# GNSS.net
KiCad netlist of a schematic drawn in Altium Designer
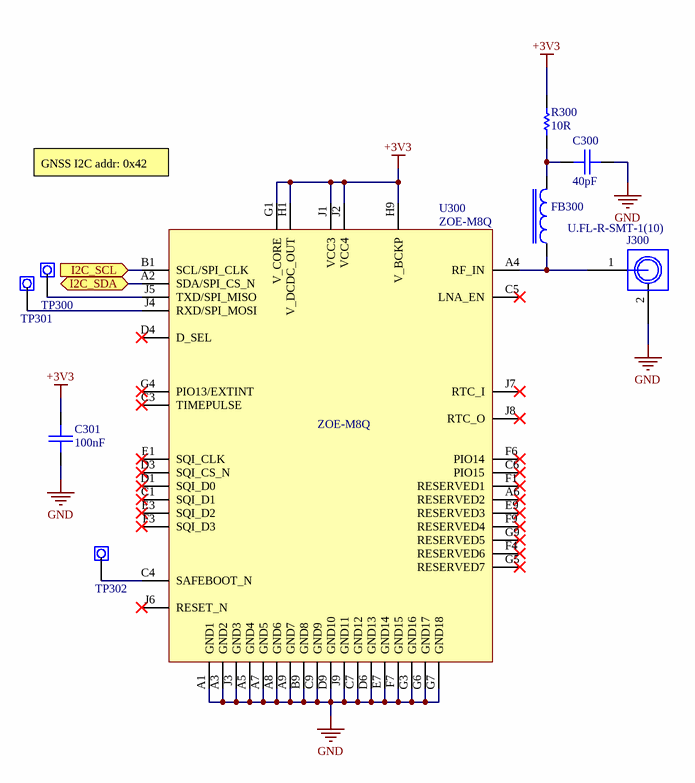
[diagram p0: GNSS.SchDoc]

(export (version "E")
  (design (tool "Eeschema 10.0.6"))
  (components
    (comp (ref "C300")
      (value "40pF")
      (footprint "0603_CAP")
      (libsource (lib "Moonlight_Components") (part "Capacitor"))
    )
    (comp (ref "C301")
      (value "100nF")
      (footprint "0603_CAP")
      (libsource (lib "Moonlight_Components") (part "Capacitor"))
    )
    (comp (ref "FB300")
      (value "FBTH1608HL221-T")
      (footprint "0603_FERRITE")
      (description "Digikey part no.\r\n587-FBTH1608HL221-TCT-ND")
      (libsource (lib "Moonlight_Components") (part "Ferrite Bead"))
    )
    (comp (ref "J300")
      (value "U.FL-R-SMT-1(10)")
      (footprint "U.FL-R-SMT-1(10)")
      (description "Digikey part no. H11891CT-ND")
      (libsource (lib "Moonlight_Components") (part "U.FL SMD"))
    )
    (comp (ref "R300")
      (value "10R")
      (footprint "0603_RES")
      (libsource (lib "Moonlight_Components") (part "Resistor"))
    )
    (comp (ref "TP300")
      (value "GPS_TX")
      (footprint "Testpoint")
      (libsource (lib "Moonlight_Components") (part "Testpoint"))
    )
    (comp (ref "TP301")
      (value "GPS_RX")
      (footprint "Testpoint")
      (libsource (lib "Moonlight_Components") (part "Testpoint"))
    )
    (comp (ref "TP302")
      (value "GPS_SAFEBOOT")
      (footprint "Testpoint2")
      (libsource (lib "Moonlight_Components") (part "Testpoint"))
    )
    (comp (ref "U300")
      (value "ZOE-M8Q")
      (footprint "ZOE-M8Q")
      (description "u-blox ZOE GNSS module")
      (fields (field (name "MANUFACTURER") "u-blox"))
      (libsource (lib "Moonlight_Components") (part "ZOE-M8Q"))
    )
  )
  (nets
    (net (code "1") (name "+3V3") (class "Default")
      (node (ref "C301") (pin "1") (pinfunction "1_1") (pintype "passive"))
      (node (ref "R300") (pin "1") (pinfunction "1_1") (pintype "passive"))
      (node (ref "U300") (pin "G1") (pinfunction "V_CORE_G1") (pintype "passive"))
      (node (ref "U300") (pin "H1") (pinfunction "V_DCDC_OUT_H1") (pintype "passive"))
      (node (ref "U300") (pin "H9") (pinfunction "V_BCKP_H9") (pintype "passive"))
      (node (ref "U300") (pin "J1") (pinfunction "VCC3_J1") (pintype "passive"))
      (node (ref "U300") (pin "J2") (pinfunction "VCC4_J2") (pintype "passive"))
    )
    (net (code "2") (name "/I2C_SCL") (class "Default")
      (node (ref "U300") (pin "B1") (pinfunction "SCL/SPI_CLK_B1") (pintype "passive"))
    )
    (net (code "3") (name "/I2C_SDA") (class "Default")
      (node (ref "U300") (pin "A2") (pinfunction "SDA/SPI_CS_N_A2") (pintype "passive"))
    )
    (net (code "4") (name "GND") (class "Default")
      (node (ref "C300") (pin "2") (pinfunction "2_2") (pintype "passive"))
      (node (ref "C301") (pin "2") (pinfunction "2_2") (pintype "passive"))
      (node (ref "J300") (pin "2") (pinfunction "GND_2") (pintype "passive"))
      (node (ref "U300") (pin "A1") (pinfunction "GND1_A1") (pintype "passive"))
      (node (ref "U300") (pin "A3") (pinfunction "GND2_A3") (pintype "passive"))
      (node (ref "U300") (pin "A5") (pinfunction "GND4_A5") (pintype "passive"))
      (node (ref "U300") (pin "A7") (pinfunction "GND5_A7") (pintype "passive"))
      (node (ref "U300") (pin "A8") (pinfunction "GND6_A8") (pintype "passive"))
      (node (ref "U300") (pin "A9") (pinfunction "GND7_A9") (pintype "passive"))
      (node (ref "U300") (pin "B9") (pinfunction "GND8_B9") (pintype "passive"))
      (node (ref "U300") (pin "C7") (pinfunction "GND12_C7") (pintype "passive"))
      (node (ref "U300") (pin "C9") (pinfunction "GND9_C9") (pintype "passive"))
      (node (ref "U300") (pin "D6") (pinfunction "GND13_D6") (pintype "passive"))
      (node (ref "U300") (pin "D9") (pinfunction "GND10_D9") (pintype "passive"))
      (node (ref "U300") (pin "E7") (pinfunction "GND14_E7") (pintype "passive"))
      (node (ref "U300") (pin "F7") (pinfunction "GND15_F7") (pintype "passive"))
      (node (ref "U300") (pin "G3") (pinfunction "GND16_G3") (pintype "passive"))
      (node (ref "U300") (pin "G6") (pinfunction "GND17_G6") (pintype "passive"))
      (node (ref "U300") (pin "G7") (pinfunction "GND18_G7") (pintype "passive"))
      (node (ref "U300") (pin "J3") (pinfunction "GND3_J3") (pintype "passive"))
      (node (ref "U300") (pin "J9") (pinfunction "GND11_J9") (pintype "passive"))
    )
    (net (code "5") (name "Net-(C300-Pad1)") (class "Default")
      (node (ref "C300") (pin "1") (pinfunction "1_1") (pintype "passive"))
      (node (ref "FB300") (pin "2") (pinfunction "2_2") (pintype "passive"))
      (node (ref "R300") (pin "2") (pinfunction "2_2") (pintype "passive"))
    )
    (net (code "6") (name "Net-(J300-SIG)") (class "Default")
      (node (ref "FB300") (pin "1") (pinfunction "1_1") (pintype "passive"))
      (node (ref "J300") (pin "1") (pinfunction "SIG_1") (pintype "passive"))
      (node (ref "U300") (pin "A4") (pinfunction "RF_IN_A4") (pintype "passive"))
    )
    (net (code "7") (name "Net-(U300-RXD{slash}SPI_MOSI)") (class "Default")
      (node (ref "TP301") (pin "1") (pinfunction "1_1") (pintype "passive"))
      (node (ref "U300") (pin "J4") (pinfunction "RXD/SPI_MOSI_J4") (pintype "passive"))
    )
    (net (code "8") (name "Net-(U300-SAFEBOOT_N)") (class "Default")
      (node (ref "TP302") (pin "1") (pinfunction "1_1") (pintype "passive"))
      (node (ref "U300") (pin "C4") (pinfunction "SAFEBOOT_N_C4") (pintype "passive"))
    )
    (net (code "9") (name "Net-(U300-TXD{slash}SPI_MISO)") (class "Default")
      (node (ref "TP300") (pin "1") (pinfunction "1_1") (pintype "passive"))
      (node (ref "U300") (pin "J5") (pinfunction "TXD/SPI_MISO_J5") (pintype "passive"))
    )
    (net (code "10") (name "unconnected-(U300-D_SEL-PadD4)") (class "Default")
      (node (ref "U300") (pin "D4") (pinfunction "D_SEL_D4") (pintype "passive+no_connect"))
    )
    (net (code "11") (name "unconnected-(U300-LNA_EN-PadC5)") (class "Default")
      (node (ref "U300") (pin "C5") (pinfunction "LNA_EN_C5") (pintype "passive+no_connect"))
    )
    (net (code "12") (name "unconnected-(U300-PIO13{slash}EXTINT-PadG4)") (class "Default")
      (node (ref "U300") (pin "G4") (pinfunction "PIO13/EXTINT_G4") (pintype "passive+no_connect"))
    )
    (net (code "13") (name "unconnected-(U300-PIO14-PadF6)") (class "Default")
      (node (ref "U300") (pin "F6") (pinfunction "PIO14_F6") (pintype "passive+no_connect"))
    )
    (net (code "14") (name "unconnected-(U300-PIO15-PadC6)") (class "Default")
      (node (ref "U300") (pin "C6") (pinfunction "PIO15_C6") (pintype "passive+no_connect"))
    )
    (net (code "15") (name "unconnected-(U300-RESERVED1-PadF1)") (class "Default")
      (node (ref "U300") (pin "F1") (pinfunction "RESERVED1_F1") (pintype "passive+no_connect"))
    )
    (net (code "16") (name "unconnected-(U300-RESERVED2-PadA6)") (class "Default")
      (node (ref "U300") (pin "A6") (pinfunction "RESERVED2_A6") (pintype "passive+no_connect"))
    )
    (net (code "17") (name "unconnected-(U300-RESERVED3-PadE9)") (class "Default")
      (node (ref "U300") (pin "E9") (pinfunction "RESERVED3_E9") (pintype "passive+no_connect"))
    )
    (net (code "18") (name "unconnected-(U300-RESERVED4-PadF9)") (class "Default")
      (node (ref "U300") (pin "F9") (pinfunction "RESERVED4_F9") (pintype "passive+no_connect"))
    )
    (net (code "19") (name "unconnected-(U300-RESERVED5-PadG9)") (class "Default")
      (node (ref "U300") (pin "G9") (pinfunction "RESERVED5_G9") (pintype "passive+no_connect"))
    )
    (net (code "20") (name "unconnected-(U300-RESERVED6-PadF4)") (class "Default")
      (node (ref "U300") (pin "F4") (pinfunction "RESERVED6_F4") (pintype "passive+no_connect"))
    )
    (net (code "21") (name "unconnected-(U300-RESERVED7-PadG5)") (class "Default")
      (node (ref "U300") (pin "G5") (pinfunction "RESERVED7_G5") (pintype "passive+no_connect"))
    )
    (net (code "22") (name "unconnected-(U300-RESET_N-PadJ6)") (class "Default")
      (node (ref "U300") (pin "J6") (pinfunction "RESET_N_J6") (pintype "passive+no_connect"))
    )
    (net (code "23") (name "unconnected-(U300-RTC_I-PadJ7)") (class "Default")
      (node (ref "U300") (pin "J7") (pinfunction "RTC_I_J7") (pintype "passive+no_connect"))
    )
    (net (code "24") (name "unconnected-(U300-RTC_O-PadJ8)") (class "Default")
      (node (ref "U300") (pin "J8") (pinfunction "RTC_O_J8") (pintype "passive+no_connect"))
    )
    (net (code "25") (name "unconnected-(U300-SQI_CLK-PadE1)") (class "Default")
      (node (ref "U300") (pin "E1") (pinfunction "SQI_CLK_E1") (pintype "passive+no_connect"))
    )
    (net (code "26") (name "unconnected-(U300-SQI_CS_N-PadD3)") (class "Default")
      (node (ref "U300") (pin "D3") (pinfunction "SQI_CS_N_D3") (pintype "passive+no_connect"))
    )
    (net (code "27") (name "unconnected-(U300-SQI_D0-PadD1)") (class "Default")
      (node (ref "U300") (pin "D1") (pinfunction "SQI_D0_D1") (pintype "passive+no_connect"))
    )
    (net (code "28") (name "unconnected-(U300-SQI_D1-PadC1)") (class "Default")
      (node (ref "U300") (pin "C1") (pinfunction "SQI_D1_C1") (pintype "passive+no_connect"))
    )
    (net (code "29") (name "unconnected-(U300-SQI_D2-PadE3)") (class "Default")
      (node (ref "U300") (pin "E3") (pinfunction "SQI_D2_E3") (pintype "passive+no_connect"))
    )
    (net (code "30") (name "unconnected-(U300-SQI_D3-PadF3)") (class "Default")
      (node (ref "U300") (pin "F3") (pinfunction "SQI_D3_F3") (pintype "passive+no_connect"))
    )
    (net (code "31") (name "unconnected-(U300-TIMEPULSE-PadC3)") (class "Default")
      (node (ref "U300") (pin "C3") (pinfunction "TIMEPULSE_C3") (pintype "passive+no_connect"))
    )
  )
)
